# cdrbot.net
KiCad netlist of a schematic drawn in EAGLE
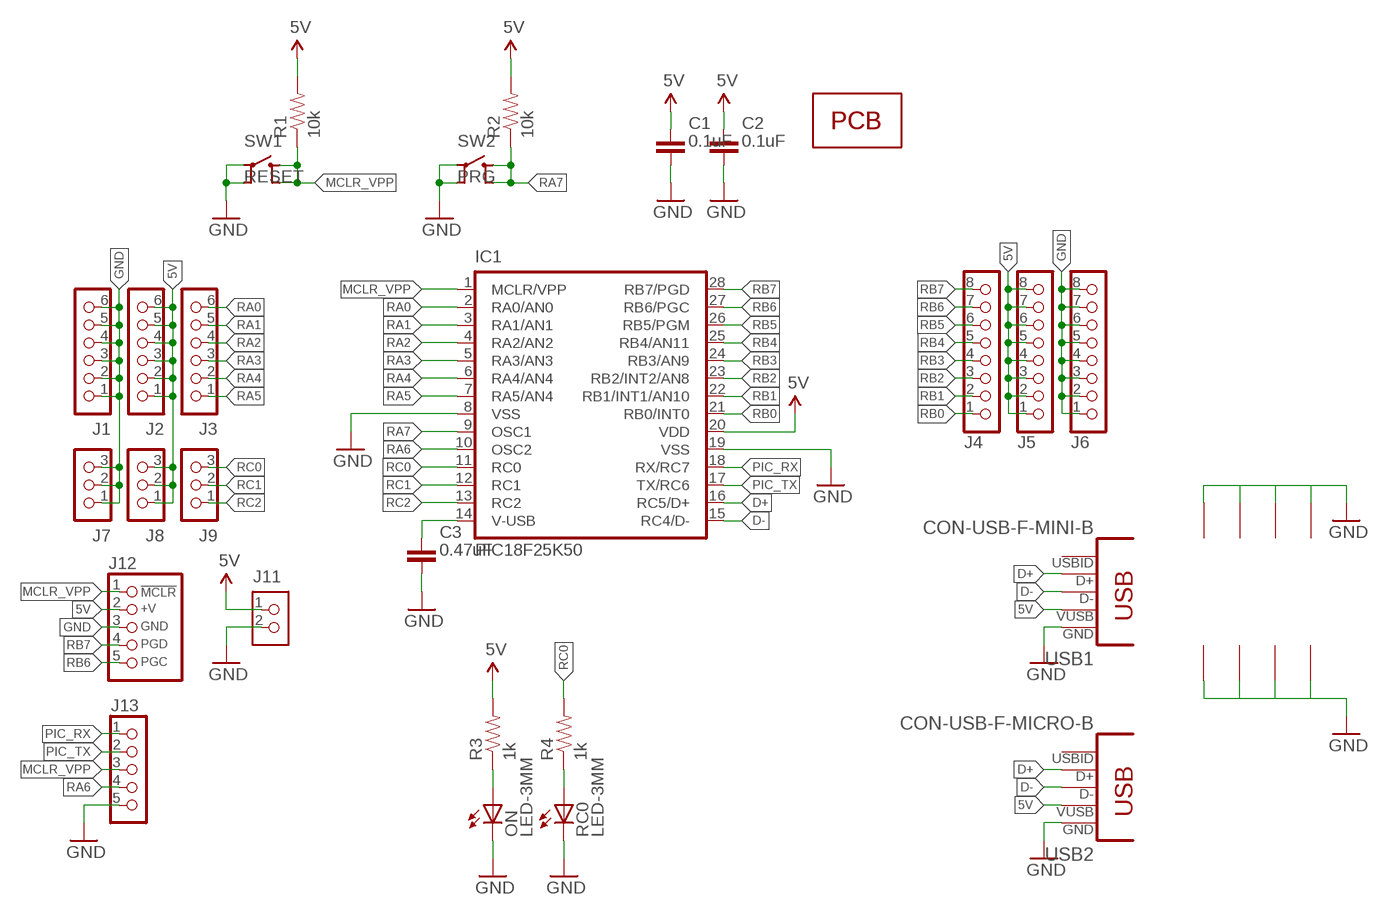
[diagram p0: schematic, sheet 1]

(export (version "E")
  (design (tool "Eeschema 10.0.6"))
  (components
    (comp (ref "C1")
      (value "0.1uF")
      (footprint "eagle-import:C025-025X050")
      (libsource (lib "eagle-import") (part "CAPACITOR-DECOUPLING"))
    )
    (comp (ref "C2")
      (value "0.1uF")
      (footprint "eagle-import:C025-025X050")
      (libsource (lib "eagle-import") (part "CAPACITOR-DECOUPLING"))
    )
    (comp (ref "C3")
      (value "0.47uF")
      (footprint "eagle-import:C025-025X050")
      (libsource (lib "eagle-import") (part "CAPACITOR-DECOUPLING"))
    )
    (comp (ref "IC1")
      (value "PIC18F25K50")
      (footprint "eagle-import:DIL-28")
      (libsource (lib "eagle-import") (part "PIC18F2550"))
    )
    (comp (ref "J1")
      (value "CON_HEADER_1X06-PTH_M")
      (footprint "eagle-import:M1X06_M")
      (libsource (lib "eagle-import") (part "CON_HEADER_1X06-PTH_M"))
    )
    (comp (ref "J2")
      (value "CON_HEADER_1X06-PTH_M")
      (footprint "eagle-import:M1X06_M")
      (libsource (lib "eagle-import") (part "CON_HEADER_1X06-PTH_M"))
    )
    (comp (ref "J3")
      (value "CON_HEADER_1X06-PTH_M")
      (footprint "eagle-import:M1X06_M")
      (libsource (lib "eagle-import") (part "CON_HEADER_1X06-PTH_M"))
    )
    (comp (ref "J4")
      (value "CON_HEADER_1X08-PTH_M")
      (footprint "eagle-import:M1X08_M")
      (libsource (lib "eagle-import") (part "CON_HEADER_1X08-PTH_M"))
    )
    (comp (ref "J5")
      (value "CON_HEADER_1X08-PTH_M")
      (footprint "eagle-import:M1X08_M")
      (libsource (lib "eagle-import") (part "CON_HEADER_1X08-PTH_M"))
    )
    (comp (ref "J6")
      (value "CON_HEADER_1X08-PTH_M")
      (footprint "eagle-import:M1X08_M")
      (libsource (lib "eagle-import") (part "CON_HEADER_1X08-PTH_M"))
    )
    (comp (ref "J7")
      (value "CON_HEADER_1X03-PTH_M")
      (footprint "eagle-import:M1X03_M")
      (libsource (lib "eagle-import") (part "CON_HEADER_1X03-PTH_M"))
    )
    (comp (ref "J8")
      (value "CON_HEADER_1X03-PTH_M")
      (footprint "eagle-import:M1X03_M")
      (libsource (lib "eagle-import") (part "CON_HEADER_1X03-PTH_M"))
    )
    (comp (ref "J9")
      (value "CON_HEADER_1X03-PTH_M")
      (footprint "eagle-import:M1X03_M")
      (libsource (lib "eagle-import") (part "CON_HEADER_1X03-PTH_M"))
    )
    (comp (ref "J11")
      (value "CON_HEADER_1X02-PTH-M")
      (footprint "eagle-import:M1X02_M")
      (libsource (lib "eagle-import") (part "CON_HEADER_1X02-PTH-M"))
    )
    (comp (ref "J12")
      (value "ICSP")
      (footprint "eagle-import:HEADER_PRG_1X05_ICSP_B")
      (libsource (lib "eagle-import") (part "CON_HEADER_PRG_PIC_ICSPB"))
    )
    (comp (ref "J13")
      (value "CON_HEADER_1X05-PTH_M")
      (footprint "eagle-import:M1X05_M")
      (libsource (lib "eagle-import") (part "CON_HEADER_1X05-PTH_M"))
    )
    (comp (ref "ON")
      (value "LED-3MM")
      (footprint "eagle-import:LED-3MM")
      (libsource (lib "eagle-import") (part "LED-3MM"))
    )
    (comp (ref "PCB1")
      (value "PCB_DP_SQUARE-5X5")
      (footprint "eagle-import:PCB5X5")
      (libsource (lib "eagle-import") (part "PCB_DP_SQUARE-5X5"))
    )
    (comp (ref "R1")
      (value "10k")
      (footprint "eagle-import:RTH025W_03")
      (libsource (lib "eagle-import") (part "RESISTOR-1/4W-0.3{dblquote}"))
    )
    (comp (ref "R2")
      (value "10k")
      (footprint "eagle-import:RTH025W_03")
      (libsource (lib "eagle-import") (part "RESISTOR-1/4W-0.3{dblquote}"))
    )
    (comp (ref "R3")
      (value "1k")
      (footprint "eagle-import:RTH025W_03")
      (libsource (lib "eagle-import") (part "RESISTOR-1/4W-0.3{dblquote}"))
    )
    (comp (ref "R4")
      (value "1k")
      (footprint "eagle-import:RTH025W_03")
      (libsource (lib "eagle-import") (part "RESISTOR-1/4W-0.3{dblquote}"))
    )
    (comp (ref "RC0")
      (value "LED-3MM")
      (footprint "eagle-import:LED-3MM")
      (libsource (lib "eagle-import") (part "LED-3MM"))
    )
    (comp (ref "SW1")
      (value "RESET")
      (footprint "eagle-import:TACTILE-PTH")
      (libsource (lib "eagle-import") (part "SWITCH-MOMPTH"))
    )
    (comp (ref "SW2")
      (value "PRG")
      (footprint "eagle-import:TACTILE-PTH")
      (libsource (lib "eagle-import") (part "SWITCH-MOMPTH"))
    )
    (comp (ref "USB1")
      (value "CON-USB-F-MINI-B")
      (footprint "eagle-import:CONN_USB_MINI-B")
      (libsource (lib "eagle-import") (part "CON-USB-F-MINI-B"))
    )
    (comp (ref "USB2")
      (value "CON-USB-F-MICRO-B")
      (footprint "eagle-import:CONN_USB_MICRO-B")
      (libsource (lib "eagle-import") (part "CON-USB-F-MICRO-B"))
    )
  )
  (nets
    (net (code "1") (name "5V") (class "Default")
      (node (ref "C1") (pin "1") (pinfunction "1_1") (pintype "passive"))
      (node (ref "C2") (pin "1") (pinfunction "1_1") (pintype "passive"))
      (node (ref "IC1") (pin "20") (pinfunction "VDD_20") (pintype "power_in"))
      (node (ref "J11") (pin "1") (pinfunction "1_1") (pintype "bidirectional"))
      (node (ref "J12") (pin "2") (pinfunction "+V_2") (pintype "passive"))
      (node (ref "J2") (pin "1") (pinfunction "1_1") (pintype "bidirectional"))
      (node (ref "J2") (pin "2") (pinfunction "2_2") (pintype "bidirectional"))
      (node (ref "J2") (pin "3") (pinfunction "3_3") (pintype "bidirectional"))
      (node (ref "J2") (pin "4") (pinfunction "4_4") (pintype "bidirectional"))
      (node (ref "J2") (pin "5") (pinfunction "5_5") (pintype "bidirectional"))
      (node (ref "J2") (pin "6") (pinfunction "6_6") (pintype "bidirectional"))
      (node (ref "J5") (pin "1") (pinfunction "1_1") (pintype "bidirectional"))
      (node (ref "J5") (pin "2") (pinfunction "2_2") (pintype "bidirectional"))
      (node (ref "J5") (pin "3") (pinfunction "3_3") (pintype "bidirectional"))
      (node (ref "J5") (pin "4") (pinfunction "4_4") (pintype "bidirectional"))
      (node (ref "J5") (pin "5") (pinfunction "5_5") (pintype "bidirectional"))
      (node (ref "J5") (pin "6") (pinfunction "6_6") (pintype "bidirectional"))
      (node (ref "J5") (pin "7") (pinfunction "7_7") (pintype "bidirectional"))
      (node (ref "J5") (pin "8") (pinfunction "8_8") (pintype "bidirectional"))
      (node (ref "J8") (pin "1") (pinfunction "1_1") (pintype "bidirectional"))
      (node (ref "J8") (pin "2") (pinfunction "2_2") (pintype "bidirectional"))
      (node (ref "J8") (pin "3") (pinfunction "3_3") (pintype "bidirectional"))
      (node (ref "R1") (pin "2") (pinfunction "2_2") (pintype "passive"))
      (node (ref "R2") (pin "2") (pinfunction "2_2") (pintype "passive"))
      (node (ref "R3") (pin "2") (pinfunction "2_2") (pintype "passive"))
      (node (ref "USB1") (pin "VUSB") (pinfunction "VUSB_VUSB") (pintype "bidirectional"))
      (node (ref "USB2") (pin "P1") (pinfunction "VUSB_P1") (pintype "bidirectional"))
    )
    (net (code "2") (name "D+") (class "Default")
      (node (ref "IC1") (pin "16") (pinfunction "RC5/D+_16") (pintype "bidirectional"))
      (node (ref "USB1") (pin "D+") (pinfunction "D+_D+") (pintype "bidirectional"))
      (node (ref "USB2") (pin "P3") (pinfunction "D+_P3") (pintype "bidirectional"))
    )
    (net (code "3") (name "D-") (class "Default")
      (node (ref "IC1") (pin "15") (pinfunction "RC4/D-_15") (pintype "bidirectional"))
      (node (ref "USB1") (pin "D-") (pinfunction "D-_D-") (pintype "bidirectional"))
      (node (ref "USB2") (pin "P2") (pinfunction "D-_P2") (pintype "bidirectional"))
    )
    (net (code "4") (name "GND") (class "Default")
      (node (ref "C1") (pin "2") (pinfunction "2_2") (pintype "passive"))
      (node (ref "C2") (pin "2") (pinfunction "2_2") (pintype "passive"))
      (node (ref "C3") (pin "2") (pinfunction "2_2") (pintype "passive"))
      (node (ref "IC1") (pin "19") (pinfunction "VSS_19") (pintype "power_in"))
      (node (ref "IC1") (pin "8") (pinfunction "VSS_8") (pintype "power_in"))
      (node (ref "J1") (pin "1") (pinfunction "1_1") (pintype "bidirectional"))
      (node (ref "J1") (pin "2") (pinfunction "2_2") (pintype "bidirectional"))
      (node (ref "J1") (pin "3") (pinfunction "3_3") (pintype "bidirectional"))
      (node (ref "J1") (pin "4") (pinfunction "4_4") (pintype "bidirectional"))
      (node (ref "J1") (pin "5") (pinfunction "5_5") (pintype "bidirectional"))
      (node (ref "J1") (pin "6") (pinfunction "6_6") (pintype "bidirectional"))
      (node (ref "J11") (pin "2") (pinfunction "2_2") (pintype "bidirectional"))
      (node (ref "J12") (pin "3") (pinfunction "GND_3") (pintype "passive"))
      (node (ref "J13") (pin "5") (pinfunction "5_5") (pintype "bidirectional"))
      (node (ref "J6") (pin "1") (pinfunction "1_1") (pintype "bidirectional"))
      (node (ref "J6") (pin "2") (pinfunction "2_2") (pintype "bidirectional"))
      (node (ref "J6") (pin "3") (pinfunction "3_3") (pintype "bidirectional"))
      (node (ref "J6") (pin "4") (pinfunction "4_4") (pintype "bidirectional"))
      (node (ref "J6") (pin "5") (pinfunction "5_5") (pintype "bidirectional"))
      (node (ref "J6") (pin "6") (pinfunction "6_6") (pintype "bidirectional"))
      (node (ref "J6") (pin "7") (pinfunction "7_7") (pintype "bidirectional"))
      (node (ref "J6") (pin "8") (pinfunction "8_8") (pintype "bidirectional"))
      (node (ref "J7") (pin "1") (pinfunction "1_1") (pintype "bidirectional"))
      (node (ref "J7") (pin "2") (pinfunction "2_2") (pintype "bidirectional"))
      (node (ref "J7") (pin "3") (pinfunction "3_3") (pintype "bidirectional"))
      (node (ref "ON") (pin "K") (pinfunction "C_K") (pintype "passive"))
      (node (ref "RC0") (pin "K") (pinfunction "C_K") (pintype "passive"))
      (node (ref "SW1") (pin "1") (pinfunction "1_1") (pintype "passive"))
      (node (ref "SW1") (pin "2") (pinfunction "3_2") (pintype "passive"))
      (node (ref "SW2") (pin "1") (pinfunction "1_1") (pintype "passive"))
      (node (ref "SW2") (pin "2") (pinfunction "3_2") (pintype "passive"))
      (node (ref "USB1") (pin "BODY@1") (pinfunction "BODY_BODY@1") (pintype "tri_state"))
      (node (ref "USB1") (pin "BODY@2") (pinfunction "BODY_BODY@2") (pintype "tri_state"))
      (node (ref "USB1") (pin "BODY@3") (pinfunction "BODY_BODY@3") (pintype "tri_state"))
      (node (ref "USB1") (pin "BODY@4") (pinfunction "BODY_BODY@4") (pintype "tri_state"))
      (node (ref "USB1") (pin "GND") (pinfunction "GND_GND") (pintype "bidirectional"))
      (node (ref "USB2") (pin "BODY@1") (pinfunction "BODY_BODY@1") (pintype "tri_state"))
      (node (ref "USB2") (pin "BODY@2") (pinfunction "BODY_BODY@2") (pintype "tri_state"))
      (node (ref "USB2") (pin "BODY@3") (pinfunction "BODY_BODY@3") (pintype "tri_state"))
      (node (ref "USB2") (pin "BODY@4") (pinfunction "BODY_BODY@4") (pintype "tri_state"))
      (node (ref "USB2") (pin "P5") (pinfunction "GND_P5") (pintype "bidirectional"))
    )
    (net (code "5") (name "MCLR_VPP") (class "Default")
      (node (ref "IC1") (pin "1") (pinfunction "MCLR/VPP_1") (pintype "bidirectional"))
      (node (ref "J12") (pin "1") (pinfunction "/MCLR_1") (pintype "passive"))
      (node (ref "J13") (pin "3") (pinfunction "3_3") (pintype "bidirectional"))
      (node (ref "R1") (pin "1") (pinfunction "1_1") (pintype "passive"))
      (node (ref "SW1") (pin "3") (pinfunction "2_3") (pintype "passive"))
      (node (ref "SW1") (pin "4") (pinfunction "4_4") (pintype "passive"))
    )
    (net (code "6") (name "Net-(IC1-V-USB)") (class "Default")
      (node (ref "C3") (pin "1") (pinfunction "1_1") (pintype "passive"))
      (node (ref "IC1") (pin "14") (pinfunction "V-USB_14") (pintype "bidirectional"))
    )
    (net (code "7") (name "Net-(ON-PadA)") (class "Default")
      (node (ref "ON") (pin "A") (pinfunction "A_A") (pintype "passive"))
      (node (ref "R3") (pin "1") (pinfunction "1_1") (pintype "passive"))
    )
    (net (code "8") (name "Net-(R4-Pad1)") (class "Default")
      (node (ref "R4") (pin "1") (pinfunction "1_1") (pintype "passive"))
      (node (ref "RC0") (pin "A") (pinfunction "A_A") (pintype "passive"))
    )
    (net (code "9") (name "PIC_RX") (class "Default")
      (node (ref "IC1") (pin "18") (pinfunction "RX/RC7_18") (pintype "input"))
      (node (ref "J13") (pin "1") (pinfunction "1_1") (pintype "bidirectional"))
    )
    (net (code "10") (name "PIC_TX") (class "Default")
      (node (ref "IC1") (pin "17") (pinfunction "TX/RC6_17") (pintype "bidirectional"))
      (node (ref "J13") (pin "2") (pinfunction "2_2") (pintype "bidirectional"))
    )
    (net (code "11") (name "RA0") (class "Default")
      (node (ref "IC1") (pin "2") (pinfunction "RA0/AN0_2") (pintype "bidirectional"))
      (node (ref "J3") (pin "6") (pinfunction "6_6") (pintype "bidirectional"))
    )
    (net (code "12") (name "RA1") (class "Default")
      (node (ref "IC1") (pin "3") (pinfunction "RA1/AN1_3") (pintype "bidirectional"))
      (node (ref "J3") (pin "5") (pinfunction "5_5") (pintype "bidirectional"))
    )
    (net (code "13") (name "RA2") (class "Default")
      (node (ref "IC1") (pin "4") (pinfunction "RA2/AN2_4") (pintype "bidirectional"))
      (node (ref "J3") (pin "4") (pinfunction "4_4") (pintype "bidirectional"))
    )
    (net (code "14") (name "RA3") (class "Default")
      (node (ref "IC1") (pin "5") (pinfunction "RA3/AN3_5") (pintype "bidirectional"))
      (node (ref "J3") (pin "3") (pinfunction "3_3") (pintype "bidirectional"))
    )
    (net (code "15") (name "RA4") (class "Default")
      (node (ref "IC1") (pin "6") (pinfunction "RA4/AN4_6") (pintype "bidirectional"))
      (node (ref "J3") (pin "2") (pinfunction "2_2") (pintype "bidirectional"))
    )
    (net (code "16") (name "RA5") (class "Default")
      (node (ref "IC1") (pin "7") (pinfunction "RA5/AN4_7") (pintype "bidirectional"))
      (node (ref "J3") (pin "1") (pinfunction "1_1") (pintype "bidirectional"))
    )
    (net (code "17") (name "RA6") (class "Default")
      (node (ref "IC1") (pin "10") (pinfunction "OSC2_10") (pintype "bidirectional"))
      (node (ref "J13") (pin "4") (pinfunction "4_4") (pintype "bidirectional"))
    )
    (net (code "18") (name "RA7") (class "Default")
      (node (ref "IC1") (pin "9") (pinfunction "OSC1_9") (pintype "bidirectional"))
      (node (ref "R2") (pin "1") (pinfunction "1_1") (pintype "passive"))
      (node (ref "SW2") (pin "3") (pinfunction "2_3") (pintype "passive"))
      (node (ref "SW2") (pin "4") (pinfunction "4_4") (pintype "passive"))
    )
    (net (code "19") (name "RB0") (class "Default")
      (node (ref "IC1") (pin "21") (pinfunction "RB0/INT0_21") (pintype "bidirectional"))
      (node (ref "J4") (pin "1") (pinfunction "1_1") (pintype "bidirectional"))
    )
    (net (code "20") (name "RB1") (class "Default")
      (node (ref "IC1") (pin "22") (pinfunction "RB1/INT1/AN10_22") (pintype "bidirectional"))
      (node (ref "J4") (pin "2") (pinfunction "2_2") (pintype "bidirectional"))
    )
    (net (code "21") (name "RB2") (class "Default")
      (node (ref "IC1") (pin "23") (pinfunction "RB2/INT2/AN8_23") (pintype "bidirectional"))
      (node (ref "J4") (pin "3") (pinfunction "3_3") (pintype "bidirectional"))
    )
    (net (code "22") (name "RB3") (class "Default")
      (node (ref "IC1") (pin "24") (pinfunction "RB3/AN9_24") (pintype "bidirectional"))
      (node (ref "J4") (pin "4") (pinfunction "4_4") (pintype "bidirectional"))
    )
    (net (code "23") (name "RB4") (class "Default")
      (node (ref "IC1") (pin "25") (pinfunction "RB4/AN11_25") (pintype "bidirectional"))
      (node (ref "J4") (pin "5") (pinfunction "5_5") (pintype "bidirectional"))
    )
    (net (code "24") (name "RB5") (class "Default")
      (node (ref "IC1") (pin "26") (pinfunction "RB5/PGM_26") (pintype "bidirectional"))
      (node (ref "J4") (pin "6") (pinfunction "6_6") (pintype "bidirectional"))
    )
    (net (code "25") (name "RB6") (class "Default")
      (node (ref "IC1") (pin "27") (pinfunction "RB6/PGC_27") (pintype "bidirectional"))
      (node (ref "J12") (pin "5") (pinfunction "PGC_5") (pintype "passive"))
      (node (ref "J4") (pin "7") (pinfunction "7_7") (pintype "bidirectional"))
    )
    (net (code "26") (name "RB7") (class "Default")
      (node (ref "IC1") (pin "28") (pinfunction "RB7/PGD_28") (pintype "bidirectional"))
      (node (ref "J12") (pin "4") (pinfunction "PGD_4") (pintype "passive"))
      (node (ref "J4") (pin "8") (pinfunction "8_8") (pintype "bidirectional"))
    )
    (net (code "27") (name "RC0") (class "Default")
      (node (ref "IC1") (pin "11") (pinfunction "RC0_11") (pintype "bidirectional"))
      (node (ref "J9") (pin "3") (pinfunction "3_3") (pintype "bidirectional"))
      (node (ref "R4") (pin "2") (pinfunction "2_2") (pintype "passive"))
    )
    (net (code "28") (name "RC1") (class "Default")
      (node (ref "IC1") (pin "12") (pinfunction "RC1_12") (pintype "bidirectional"))
      (node (ref "J9") (pin "2") (pinfunction "2_2") (pintype "bidirectional"))
    )
    (net (code "29") (name "RC2") (class "Default")
      (node (ref "IC1") (pin "13") (pinfunction "RC2_13") (pintype "bidirectional"))
      (node (ref "J9") (pin "1") (pinfunction "1_1") (pintype "bidirectional"))
    )
    (net (code "30") (name "unconnected-(USB1B-USBID-PadID)") (class "Default")
      (node (ref "USB1") (pin "ID") (pinfunction "USBID_ID") (pintype "bidirectional"))
    )
    (net (code "31") (name "unconnected-(USB2B-USBID-PadP4)") (class "Default")
      (node (ref "USB2") (pin "P4") (pinfunction "USBID_P4") (pintype "bidirectional"))
    )
  )
)
